# AETEL_Pocket_PoV.net
KiCad netlist of a schematic drawn in EAGLE
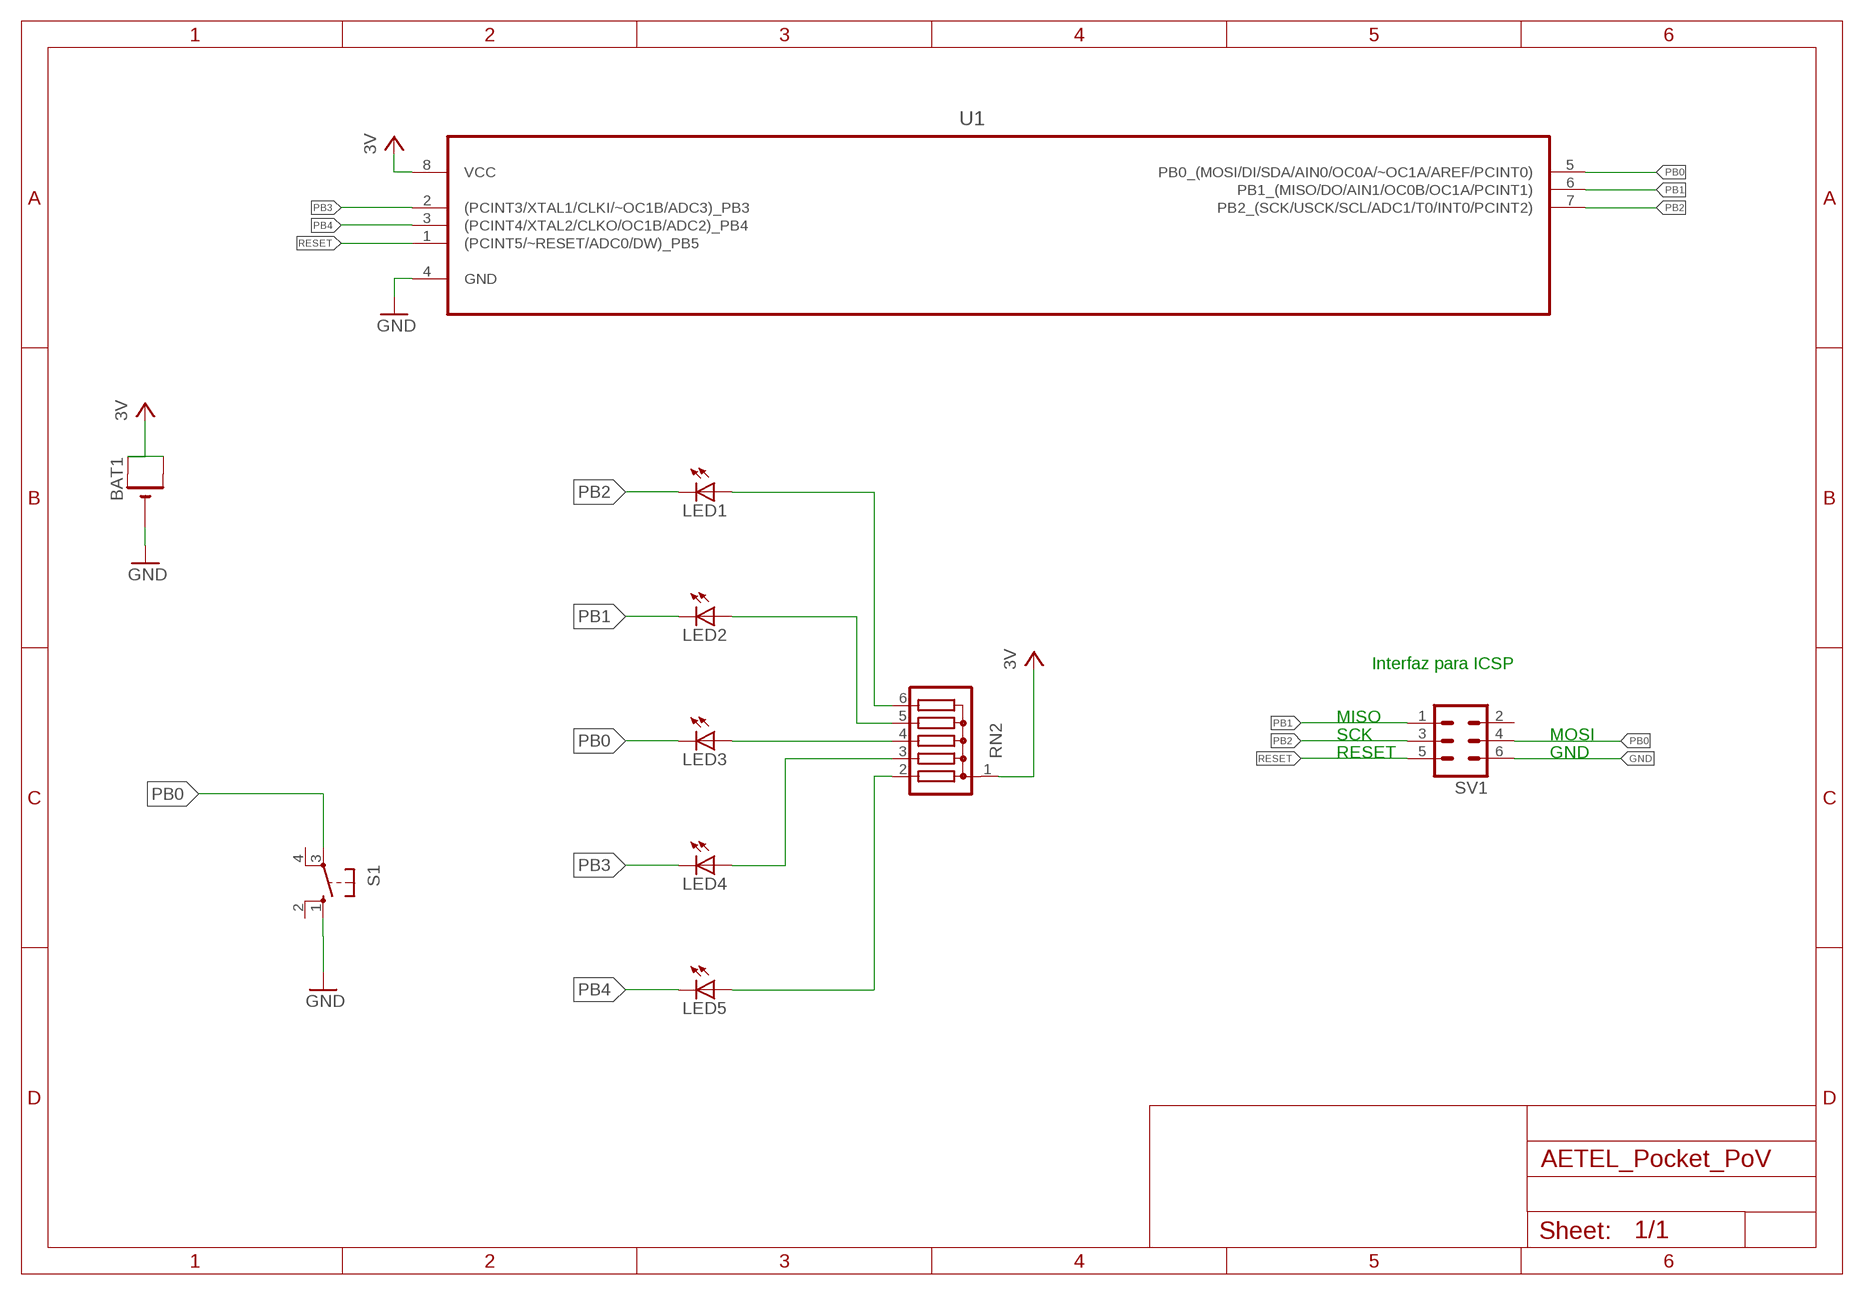
[diagram p0: schematic, sheet 1]

(export (version "E")
  (design (tool "Eeschema 10.0.6"))
  (components
    (comp (ref "BAT1")
      (value "CR2032THM")
      (footprint "eagle-import:CR2032-THRU")
      (libsource (lib "eagle-import") (part "CR2032THM"))
    )
    (comp (ref "LED1")
      (value "LEDSQUARE_LED5MM")
      (footprint "eagle-import:SQUARE_LED5MM")
      (libsource (lib "eagle-import") (part "LEDSQUARE_LED5MM"))
    )
    (comp (ref "LED2")
      (value "LEDSQUARE_LED5MM")
      (footprint "eagle-import:SQUARE_LED5MM")
      (libsource (lib "eagle-import") (part "LEDSQUARE_LED5MM"))
    )
    (comp (ref "LED3")
      (value "LEDSQUARE_LED5MM")
      (footprint "eagle-import:SQUARE_LED5MM")
      (libsource (lib "eagle-import") (part "LEDSQUARE_LED5MM"))
    )
    (comp (ref "LED4")
      (value "LEDSQUARE_LED5MM")
      (footprint "eagle-import:SQUARE_LED5MM")
      (libsource (lib "eagle-import") (part "LEDSQUARE_LED5MM"))
    )
    (comp (ref "LED5")
      (value "LEDSQUARE_LED5MM")
      (footprint "eagle-import:SQUARE_LED5MM")
      (libsource (lib "eagle-import") (part "LEDSQUARE_LED5MM"))
    )
    (comp (ref "RN2")
      (value "G05R")
      (footprint "eagle-import:SIL6")
      (libsource (lib "eagle-import") (part "G05R"))
    )
    (comp (ref "S1")
      (value "10-XX")
      (footprint "eagle-import:B3F-10XX")
      (fields (field (name "MPN") "B3F-1000"))
      (libsource (lib "eagle-import") (part "10-XX"))
    )
    (comp (ref "SV1")
      (value "MA03-2")
      (footprint "eagle-import:MA03-2")
      (libsource (lib "eagle-import") (part "MA03-2"))
    )
    (comp (ref "U1")
      (value "ATTINY85-20PU")
      (footprint "eagle-import:DIP254P762X533-8")
      (libsource (lib "eagle-import") (part "ATTINY85-20PU"))
    )
  )
  (nets
    (net (code "1") (name "3V") (class "Default")
      (node (ref "BAT1") (pin "+1") (pinfunction "+_+1") (pintype "passive"))
      (node (ref "BAT1") (pin "+2") (pinfunction "+1_+2") (pintype "passive"))
      (node (ref "RN2") (pin "1") (pinfunction "1_1") (pintype "passive"))
      (node (ref "U1") (pin "8") (pinfunction "VCC_8") (pintype "power_in"))
    )
    (net (code "2") (name "GND") (class "Default")
      (node (ref "BAT1") (pin "-") (pinfunction "-_-") (pintype "passive"))
      (node (ref "S1") (pin "1") (pinfunction "S_1") (pintype "passive"))
      (node (ref "SV1") (pin "6") (pinfunction "6_6") (pintype "passive"))
      (node (ref "U1") (pin "4") (pinfunction "GND_4") (pintype "passive"))
    )
    (net (code "3") (name "Net-(LED1-PadA)") (class "Default")
      (node (ref "LED1") (pin "A") (pinfunction "A_A") (pintype "passive"))
      (node (ref "RN2") (pin "6") (pinfunction "6_6") (pintype "passive"))
    )
    (net (code "4") (name "Net-(LED2-PadA)") (class "Default")
      (node (ref "LED2") (pin "A") (pinfunction "A_A") (pintype "passive"))
      (node (ref "RN2") (pin "5") (pinfunction "5_5") (pintype "passive"))
    )
    (net (code "5") (name "Net-(LED3-PadA)") (class "Default")
      (node (ref "LED3") (pin "A") (pinfunction "A_A") (pintype "passive"))
      (node (ref "RN2") (pin "4") (pinfunction "4_4") (pintype "passive"))
    )
    (net (code "6") (name "Net-(LED4-PadA)") (class "Default")
      (node (ref "LED4") (pin "A") (pinfunction "A_A") (pintype "passive"))
      (node (ref "RN2") (pin "3") (pinfunction "3_3") (pintype "passive"))
    )
    (net (code "7") (name "Net-(LED5-PadA)") (class "Default")
      (node (ref "LED5") (pin "A") (pinfunction "A_A") (pintype "passive"))
      (node (ref "RN2") (pin "2") (pinfunction "2_2") (pintype "passive"))
    )
    (net (code "8") (name "PB0") (class "Default")
      (node (ref "LED3") (pin "K") (pinfunction "C_K") (pintype "passive"))
      (node (ref "S1") (pin "3") (pinfunction "P_3") (pintype "passive"))
      (node (ref "SV1") (pin "4") (pinfunction "4_4") (pintype "passive"))
      (node (ref "U1") (pin "5") (pinfunction "PB0_(MOSI/DI/SDA/AIN0/OC0A/~{OC1A/AREF/PCINT0})_5") (pintype "bidirectional"))
    )
    (net (code "9") (name "PB1") (class "Default")
      (node (ref "LED2") (pin "K") (pinfunction "C_K") (pintype "passive"))
      (node (ref "SV1") (pin "1") (pinfunction "1_1") (pintype "passive"))
      (node (ref "U1") (pin "6") (pinfunction "PB1_(MISO/DO/AIN1/OC0B/OC1A/PCINT1)_6") (pintype "bidirectional"))
    )
    (net (code "10") (name "PB2") (class "Default")
      (node (ref "LED1") (pin "K") (pinfunction "C_K") (pintype "passive"))
      (node (ref "SV1") (pin "3") (pinfunction "3_3") (pintype "passive"))
      (node (ref "U1") (pin "7") (pinfunction "PB2_(SCK/USCK/SCL/ADC1/T0/INT0/PCINT2)_7") (pintype "bidirectional"))
    )
    (net (code "11") (name "PB3") (class "Default")
      (node (ref "LED4") (pin "K") (pinfunction "C_K") (pintype "passive"))
      (node (ref "U1") (pin "2") (pinfunction "(PCINT3/XTAL1/CLKI/~{OC1B/ADC3})_PB3_2") (pintype "bidirectional"))
    )
    (net (code "12") (name "PB4") (class "Default")
      (node (ref "LED5") (pin "K") (pinfunction "C_K") (pintype "passive"))
      (node (ref "U1") (pin "3") (pinfunction "(PCINT4/XTAL2/CLKO/OC1B/ADC2)_PB4_3") (pintype "bidirectional"))
    )
    (net (code "13") (name "RESET") (class "Default")
      (node (ref "SV1") (pin "5") (pinfunction "5_5") (pintype "passive"))
      (node (ref "U1") (pin "1") (pinfunction "(PCINT5/~{RESET/ADC0/DW})_PB5_1") (pintype "bidirectional"))
    )
    (net (code "14") (name "unconnected-(S1-P1-Pad4)") (class "Default")
      (node (ref "S1") (pin "4") (pinfunction "P1_4") (pintype "passive"))
    )
    (net (code "15") (name "unconnected-(S1-S1-Pad2)") (class "Default")
      (node (ref "S1") (pin "2") (pinfunction "S1_2") (pintype "passive"))
    )
    (net (code "16") (name "unconnected-(SV1-Pad2)") (class "Default")
      (node (ref "SV1") (pin "2") (pinfunction "2_2") (pintype "passive"))
    )
  )
)
